# 220VAC-28VDC_Converter.net
KiCad netlist of a schematic drawn in EAGLE
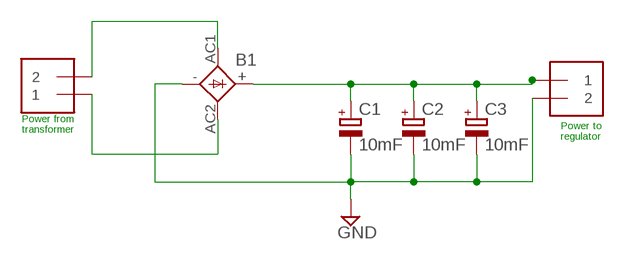
[diagram p0: schematic, sheet 1]

(export (version "E")
  (design (tool "Eeschema 10.0.6"))
  (components
    (comp (ref "B1")
      (value "KBU")
      (footprint "eagle-import:KBU")
      (libsource (lib "eagle-import") (part "KBU"))
    )
    (comp (ref "C1")
      (value "10mF")
      (footprint "eagle-import:EB35D")
      (libsource (lib "eagle-import") (part "CPOL-EUE10-35"))
    )
    (comp (ref "C2")
      (value "10mF")
      (footprint "eagle-import:EB35D")
      (libsource (lib "eagle-import") (part "CPOL-EUE10-35"))
    )
    (comp (ref "C3")
      (value "10mF")
      (footprint "eagle-import:EB35D")
      (libsource (lib "eagle-import") (part "CPOL-EUE10-35"))
    )
    (comp (ref "J1")
      (value "1X2-3.5MM")
      (footprint "eagle-import:1X2-3.5MM")
      (libsource (lib "eagle-import") (part "1X2-3.5MM"))
    )
    (comp (ref "J2")
      (value "1X2-3.5MM")
      (footprint "eagle-import:1X2-3.5MM")
      (libsource (lib "eagle-import") (part "1X2-3.5MM"))
    )
  )
  (nets
    (net (code "1") (name "GND") (class "Default")
      (node (ref "B1") (pin "-") (pinfunction "-_-") (pintype "passive"))
      (node (ref "C1") (pin "-") (pinfunction "-_-") (pintype "passive"))
      (node (ref "C2") (pin "-") (pinfunction "-_-") (pintype "passive"))
      (node (ref "C3") (pin "-") (pinfunction "-_-") (pintype "passive"))
      (node (ref "J2") (pin "2") (pinfunction "2_2") (pintype "passive"))
    )
    (net (code "2") (name "Net-(B1-Pad+)") (class "Default")
      (node (ref "B1") (pin "+") (pinfunction "+_+") (pintype "passive"))
      (node (ref "C1") (pin "+") (pinfunction "+_+") (pintype "passive"))
      (node (ref "C2") (pin "+") (pinfunction "+_+") (pintype "passive"))
      (node (ref "C3") (pin "+") (pinfunction "+_+") (pintype "passive"))
      (node (ref "J2") (pin "1") (pinfunction "1_1") (pintype "passive"))
    )
    (net (code "3") (name "Net-(B1-PadAC1)") (class "Default")
      (node (ref "B1") (pin "AC1") (pinfunction "AC1_AC1") (pintype "passive"))
      (node (ref "J1") (pin "2") (pinfunction "2_2") (pintype "passive"))
    )
    (net (code "4") (name "Net-(B1-PadAC2)") (class "Default")
      (node (ref "B1") (pin "AC2") (pinfunction "AC2_AC2") (pintype "passive"))
      (node (ref "J1") (pin "1") (pinfunction "1_1") (pintype "passive"))
    )
  )
)
